# HVcontroller0_1.net
KiCad netlist of a schematic drawn in EAGLE
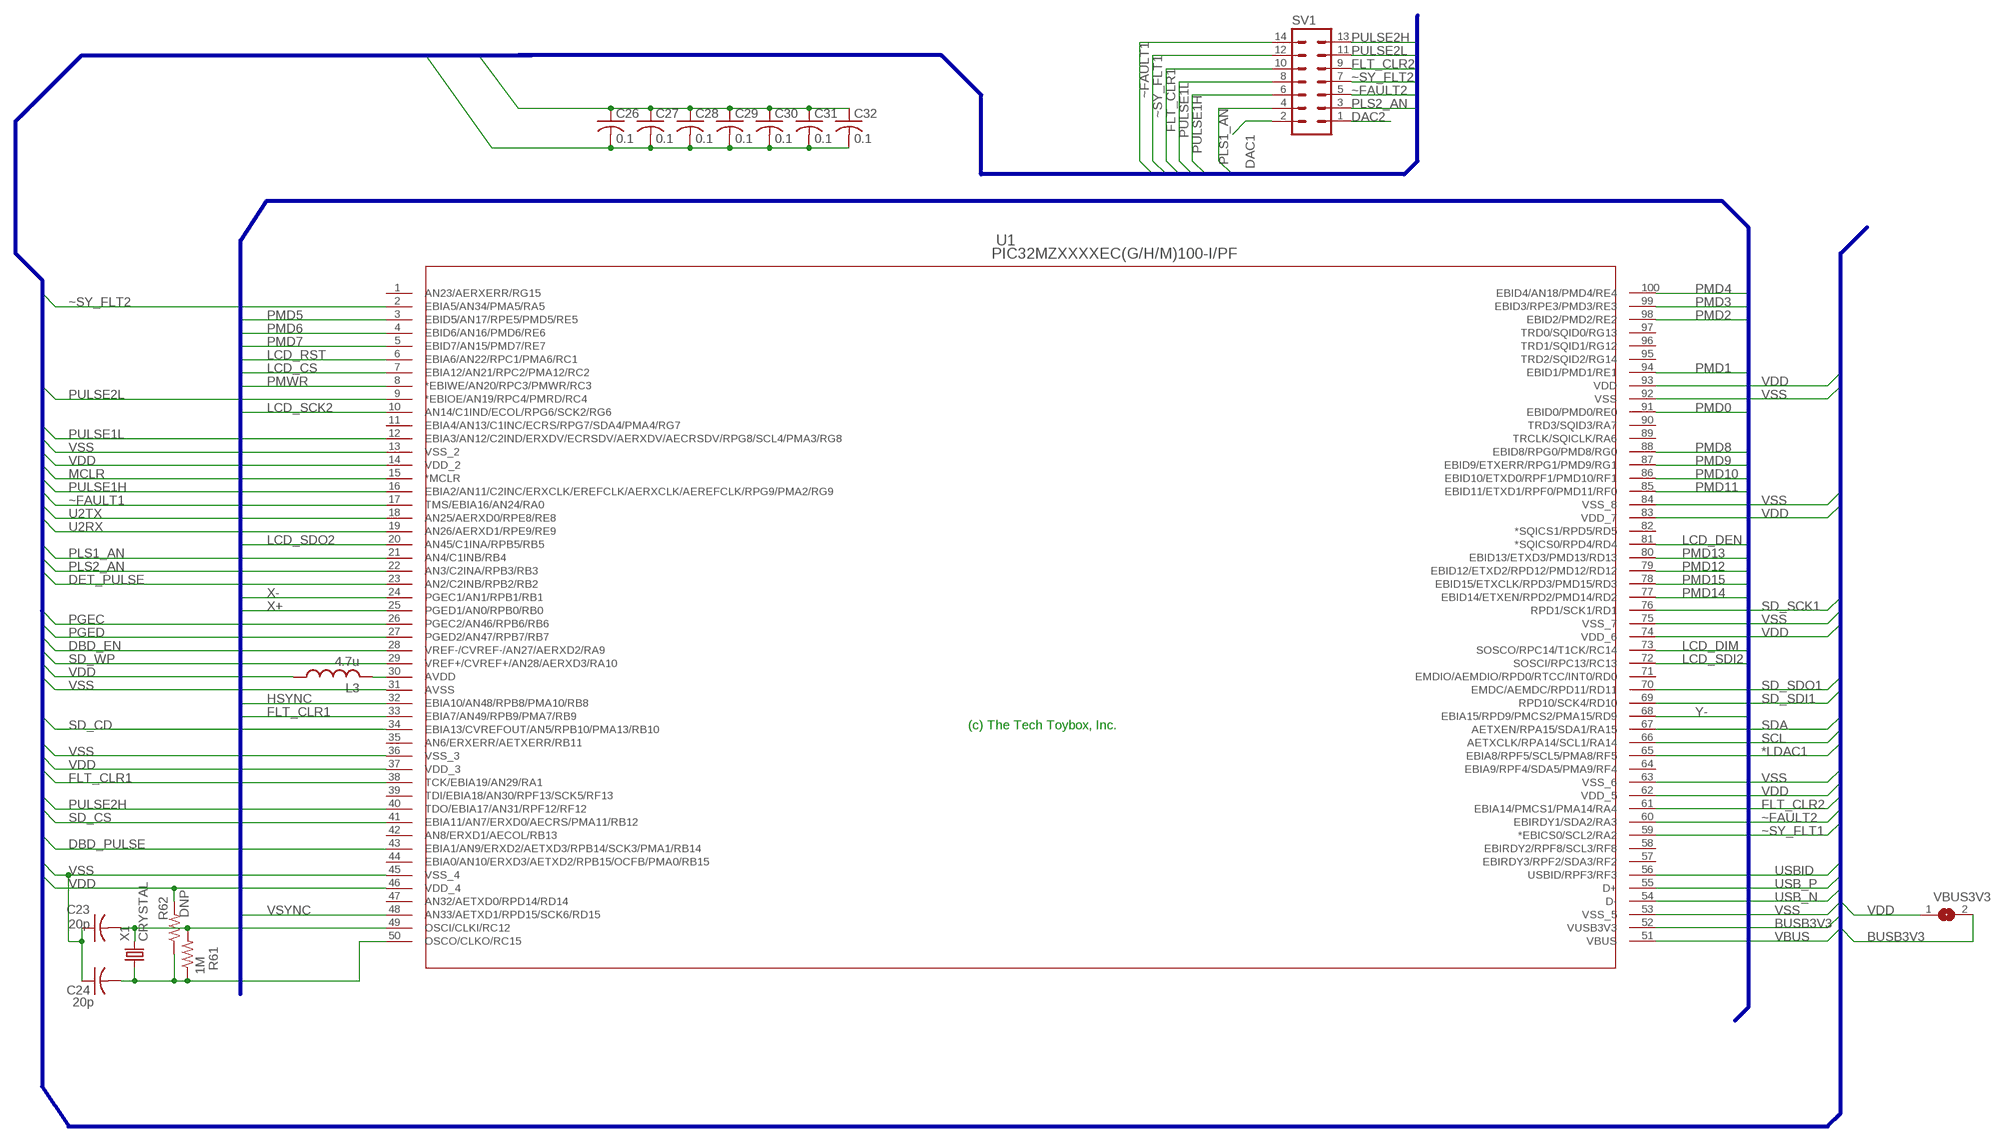
[diagram p0: schematic, sheet 1]
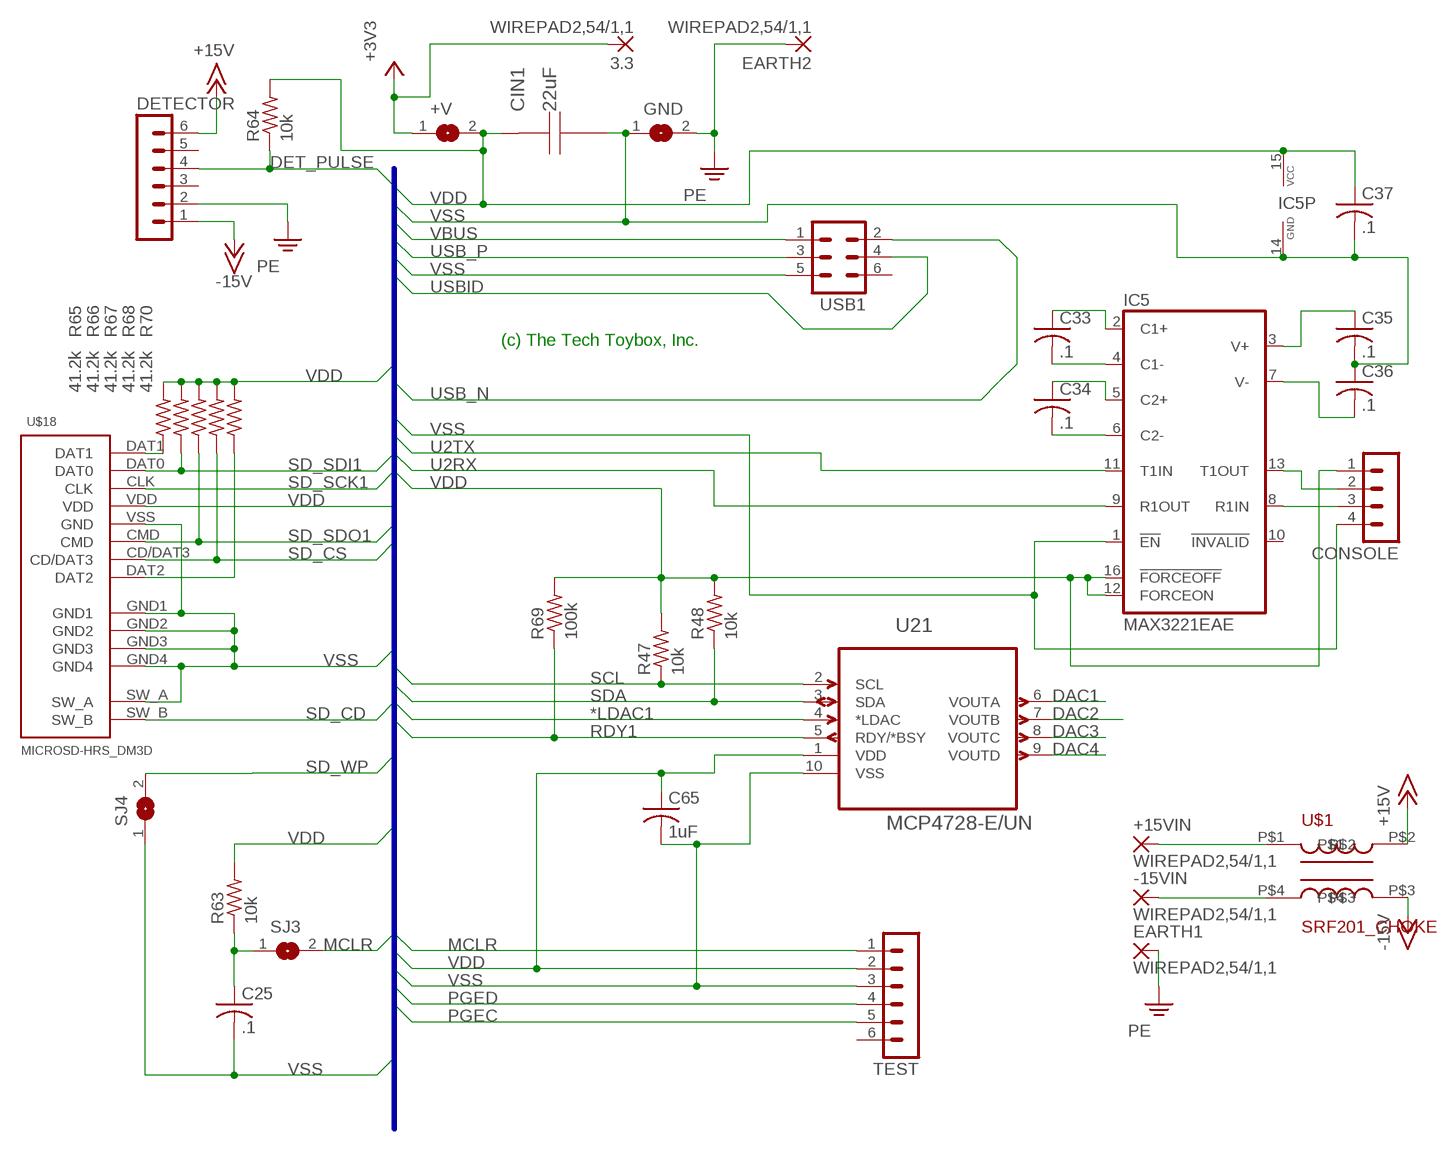
[diagram p1: schematic, sheet 2]

(export (version "E")
  (design (tool "Eeschema 10.0.6"))
  (components
    (comp (ref "C23")
      (value "20p")
      (footprint "eagle-import:C0402")
      (libsource (lib "eagle-import") (part "C-USC0402"))
    )
    (comp (ref "C24")
      (value "20p")
      (footprint "eagle-import:C0402")
      (libsource (lib "eagle-import") (part "C-USC0402"))
    )
    (comp (ref "C26")
      (value "0.1")
      (footprint "eagle-import:C0603")
      (libsource (lib "eagle-import") (part "C-USC0603"))
    )
    (comp (ref "C27")
      (value "0.1")
      (footprint "eagle-import:C0603")
      (libsource (lib "eagle-import") (part "C-USC0603"))
    )
    (comp (ref "C28")
      (value "0.1")
      (footprint "eagle-import:C0603")
      (libsource (lib "eagle-import") (part "C-USC0603"))
    )
    (comp (ref "C29")
      (value "0.1")
      (footprint "eagle-import:C0603")
      (libsource (lib "eagle-import") (part "C-USC0603"))
    )
    (comp (ref "C30")
      (value "0.1")
      (footprint "eagle-import:C0603")
      (libsource (lib "eagle-import") (part "C-USC0603"))
    )
    (comp (ref "C31")
      (value "0.1")
      (footprint "eagle-import:C0603")
      (libsource (lib "eagle-import") (part "C-USC0603"))
    )
    (comp (ref "C32")
      (value "0.1")
      (footprint "eagle-import:C0603")
      (libsource (lib "eagle-import") (part "C-USC0603"))
    )
    (comp (ref "L3")
      (value "4.7u")
      (footprint "eagle-import:L2012C")
      (libsource (lib "eagle-import") (part "L-USL2012C"))
    )
    (comp (ref "R61")
      (value "1M")
      (footprint "eagle-import:R0402")
      (libsource (lib "eagle-import") (part "R-US_R0402"))
    )
    (comp (ref "R62")
      (value "DNP")
      (footprint "eagle-import:R0402")
      (libsource (lib "eagle-import") (part "R-US_R0402"))
    )
    (comp (ref "SV1")
      (value "MA07-2")
      (footprint "eagle-import:MA07-2")
      (libsource (lib "eagle-import") (part "MA07-2"))
    )
    (comp (ref "U1")
      (value "PIC32MZXXXXEC(G/H/M)100-I/PF")
      (footprint "eagle-import:TQFP100_14X14MC")
      (fields (field (name "MANUFACTURER_PART_NUMBER") "pic32mz1024ecg100-i/pf"))
      (libsource (lib "eagle-import") (part "PIC32MZXXXXEC(G/H/M)100-I/PF"))
    )
    (comp (ref "VBUS3V3")
      (value "SJ")
      (footprint "eagle-import:SJ")
      (libsource (lib "eagle-import") (part "SJ"))
    )
    (comp (ref "X1")
      (value "CRYSTAL")
      (footprint "eagle-import:ABM")
      (libsource (lib "eagle-import") (part "CRYSTAL"))
    )
    (comp (ref "+15VIN")
      (value "WIREPAD2,54/1,1")
      (footprint "eagle-import:2,54_1,1")
      (libsource (lib "eagle-import") (part "WIREPAD2,54/1,1"))
    )
    (comp (ref "+V")
      (value "SJW")
      (footprint "eagle-import:SJW")
      (libsource (lib "eagle-import") (part "SJW"))
    )
    (comp (ref "-15VIN")
      (value "WIREPAD2,54/1,1")
      (footprint "eagle-import:2,54_1,1")
      (libsource (lib "eagle-import") (part "WIREPAD2,54/1,1"))
    )
    (comp (ref "3.3")
      (value "WIREPAD2,54/1,1")
      (footprint "eagle-import:2,54_1,1")
      (libsource (lib "eagle-import") (part "WIREPAD2,54/1,1"))
    )
    (comp (ref "C25")
      (value ".1")
      (footprint "eagle-import:C0402")
      (libsource (lib "eagle-import") (part "C-USC0402"))
    )
    (comp (ref "C33")
      (value ".1")
      (footprint "eagle-import:C0402")
      (libsource (lib "eagle-import") (part "C-USC0402"))
    )
    (comp (ref "C34")
      (value ".1")
      (footprint "eagle-import:C0402")
      (libsource (lib "eagle-import") (part "C-USC0402"))
    )
    (comp (ref "C35")
      (value ".1")
      (footprint "eagle-import:C0402")
      (libsource (lib "eagle-import") (part "C-USC0402"))
    )
    (comp (ref "C36")
      (value ".1")
      (footprint "eagle-import:C0402")
      (libsource (lib "eagle-import") (part "C-USC0402"))
    )
    (comp (ref "C37")
      (value ".1")
      (footprint "eagle-import:C0402")
      (libsource (lib "eagle-import") (part "C-USC0402"))
    )
    (comp (ref "C65")
      (value "1uF")
      (footprint "eagle-import:C0402")
      (libsource (lib "eagle-import") (part "C-USC0402"))
    )
    (comp (ref "CIN1")
      (value "22uF")
      (footprint "eagle-import:1210")
      (fields (field (name "MANUFACTURER_PART_NUMBER") "GRM32ER61E226KE15L"))
      (libsource (lib "eagle-import") (part "GRM32ER61E226KE15L"))
    )
    (comp (ref "CONSOLE")
      (value "MA04-1")
      (footprint "eagle-import:MA04-1")
      (libsource (lib "eagle-import") (part "MA04-1"))
    )
    (comp (ref "DETECTOR")
      (value "MA06-1")
      (footprint "eagle-import:MA06-1")
      (libsource (lib "eagle-import") (part "MA06-1"))
    )
    (comp (ref "EARTH1")
      (value "WIREPAD2,54/1,1")
      (footprint "eagle-import:2,54_1,1")
      (libsource (lib "eagle-import") (part "WIREPAD2,54/1,1"))
    )
    (comp (ref "EARTH2")
      (value "WIREPAD2,54/1,1")
      (footprint "eagle-import:2,54_1,1")
      (libsource (lib "eagle-import") (part "WIREPAD2,54/1,1"))
    )
    (comp (ref "GND")
      (value "SJW")
      (footprint "eagle-import:SJW")
      (libsource (lib "eagle-import") (part "SJW"))
    )
    (comp (ref "IC5")
      (value "MAX3221EAE")
      (footprint "eagle-import:SSOP16")
      (fields (field (name "MF") "MAXIM") (field (name "MPN") "MAX3221EAE+"))
      (libsource (lib "eagle-import") (part "MAX3221AEE"))
    )
    (comp (ref "R47")
      (value "10k")
      (footprint "eagle-import:R0805")
      (libsource (lib "eagle-import") (part "R-US_R0805"))
    )
    (comp (ref "R48")
      (value "10k")
      (footprint "eagle-import:R0805")
      (libsource (lib "eagle-import") (part "R-US_R0805"))
    )
    (comp (ref "R63")
      (value "10k")
      (footprint "eagle-import:R0805")
      (libsource (lib "eagle-import") (part "R-US_R0805"))
    )
    (comp (ref "R64")
      (value "10k")
      (footprint "eagle-import:R0805")
      (libsource (lib "eagle-import") (part "R-US_R0805"))
    )
    (comp (ref "R65")
      (value "41.2k")
      (footprint "eagle-import:R0603")
      (libsource (lib "eagle-import") (part "R-US_R0603"))
    )
    (comp (ref "R66")
      (value "41.2k")
      (footprint "eagle-import:R0603")
      (libsource (lib "eagle-import") (part "R-US_R0603"))
    )
    (comp (ref "R67")
      (value "41.2k")
      (footprint "eagle-import:R0603")
      (libsource (lib "eagle-import") (part "R-US_R0603"))
    )
    (comp (ref "R68")
      (value "41.2k")
      (footprint "eagle-import:R0603")
      (libsource (lib "eagle-import") (part "R-US_R0603"))
    )
    (comp (ref "R69")
      (value "100k")
      (footprint "eagle-import:R0805")
      (libsource (lib "eagle-import") (part "R-US_R0805"))
    )
    (comp (ref "R70")
      (value "41.2k")
      (footprint "eagle-import:R0603")
      (libsource (lib "eagle-import") (part "R-US_R0603"))
    )
    (comp (ref "SJ3") (value "SJ") (footprint "eagle-import:SJ") (libsource (lib "eagle-import") (part "SJ")))
    (comp (ref "SJ4") (value "SJ") (footprint "eagle-import:SJ") (libsource (lib "eagle-import") (part "SJ")))
    (comp (ref "TEST")
      (value "MA06-1")
      (footprint "eagle-import:MA06-1")
      (libsource (lib "eagle-import") (part "MA06-1"))
    )
    (comp (ref "U$1")
      (value "SRF201_CHOKE")
      (footprint "eagle-import:CHOKE_BOURNES_SRF2012")
      (libsource (lib "eagle-import") (part "SRF201_CHOKE"))
    )
    (comp (ref "U$18")
      (value "MICROSD-HRS_DM3D")
      (footprint "eagle-import:DM3D")
      (libsource (lib "eagle-import") (part "MICROSD-HRS_DM3D"))
    )
    (comp (ref "U21")
      (value "MCP4728-E/UN")
      (footprint "eagle-import:SOP50P490X110-10N")
      (libsource (lib "eagle-import") (part "MCP4728-E/UN"))
    )
    (comp (ref "USB1")
      (value "MA03-2")
      (footprint "eagle-import:MA03-2")
      (libsource (lib "eagle-import") (part "MA03-2"))
    )
  )
  (nets
    (net (code "1") (name "*LDAC1") (class "Default")
      (node (ref "U1") (pin "65") (pinfunction "EBIA8/RPF5/SCL5/PMA8/RF5_65") (pintype "bidirectional"))
      (node (ref "U21") (pin "4") (pinfunction "*LDAC_4") (pintype "input"))
    )
    (net (code "2") (name "+3V3") (class "Default")
      (node (ref "+V") (pin "1") (pinfunction "1_1") (pintype "passive"))
      (node (ref "3.3") (pin "1") (pinfunction "P_1") (pintype "passive"))
    )
    (net (code "3") (name "+15V") (class "Default")
      (node (ref "DETECTOR") (pin "6") (pinfunction "6_6") (pintype "passive"))
      (node (ref "U$1") (pin "P$2") (pinfunction "P$2_P$2") (pintype "bidirectional"))
    )
    (net (code "4") (name "-15V") (class "Default")
      (node (ref "DETECTOR") (pin "1") (pinfunction "1_1") (pintype "passive"))
      (node (ref "U$1") (pin "P$3") (pinfunction "P$3_P$3") (pintype "bidirectional"))
    )
    (net (code "5") (name "BUSB3V3") (class "Default")
      (node (ref "U1") (pin "52") (pinfunction "VUSB3V3_52") (pintype "power_in"))
      (node (ref "VBUS3V3") (pin "2") (pinfunction "2_2") (pintype "passive"))
    )
    (net (code "6") (name "DAC1") (class "Default")
      (node (ref "SV1") (pin "2") (pinfunction "2_2") (pintype "passive"))
      (node (ref "U21") (pin "6") (pinfunction "VOUTA_6") (pintype "output"))
    )
    (net (code "7") (name "DAC2") (class "Default")
      (node (ref "SV1") (pin "1") (pinfunction "1_1") (pintype "passive"))
      (node (ref "U21") (pin "7") (pinfunction "VOUTB_7") (pintype "output"))
    )
    (net (code "8") (name "DAC3") (class "Default")
      (node (ref "U21") (pin "8") (pinfunction "VOUTC_8") (pintype "output"))
    )
    (net (code "9") (name "DAC4") (class "Default")
      (node (ref "U21") (pin "9") (pinfunction "VOUTD_9") (pintype "output"))
    )
    (net (code "10") (name "DBD_EN") (class "Default")
      (node (ref "U1") (pin "28") (pinfunction "VREF-/CVREF-/AN27/AERXD2/RA9_28") (pintype "bidirectional"))
    )
    (net (code "11") (name "DBD_PULSE") (class "Default")
      (node (ref "U1") (pin "43") (pinfunction "EBIA1/AN9/ERXD2/AETXD3/RPB14/SCK3/PMA1/RB14_43") (pintype "bidirectional"))
    )
    (net (code "12") (name "DET_PULSE") (class "Default")
      (node (ref "DETECTOR") (pin "4") (pinfunction "4_4") (pintype "passive"))
      (node (ref "R64") (pin "1") (pinfunction "1_1") (pintype "passive"))
      (node (ref "U1") (pin "23") (pinfunction "AN2/C2INB/RPB2/RB2_23") (pintype "bidirectional"))
    )
    (net (code "13") (name "FLT_CLR1") (class "Default")
      (node (ref "SV1") (pin "10") (pinfunction "10_10") (pintype "passive"))
      (node (ref "U1") (pin "38") (pinfunction "TCK/EBIA19/AN29/RA1_38") (pintype "bidirectional"))
    )
    (net (code "14") (name "FLT_CLR2") (class "Default")
      (node (ref "SV1") (pin "9") (pinfunction "9_9") (pintype "passive"))
      (node (ref "U1") (pin "61") (pinfunction "EBIA14/PMCS1/PMA14/RA4_61") (pintype "bidirectional"))
    )
    (net (code "15") (name "HSYNC") (class "Default")
      (node (ref "U1") (pin "32") (pinfunction "EBIA10/AN48/RPB8/PMA10/RB8_32") (pintype "bidirectional"))
    )
    (net (code "16") (name "LCD_CS") (class "Default")
      (node (ref "U1") (pin "7") (pinfunction "EBIA12/AN21/RPC2/PMA12/RC2_7") (pintype "bidirectional"))
    )
    (net (code "17") (name "LCD_DEN") (class "Default")
      (node (ref "U1") (pin "81") (pinfunction "*SQICS0/RPD4/RD4_81") (pintype "bidirectional"))
    )
    (net (code "18") (name "LCD_DIM") (class "Default")
      (node (ref "U1") (pin "73") (pinfunction "SOSCO/RPC14/T1CK/RC14_73") (pintype "bidirectional"))
    )
    (net (code "19") (name "LCD_RST") (class "Default")
      (node (ref "U1") (pin "6") (pinfunction "EBIA6/AN22/RPC1/PMA6/RC1_6") (pintype "bidirectional"))
    )
    (net (code "20") (name "LCD_SCK2") (class "Default")
      (node (ref "U1") (pin "10") (pinfunction "AN14/C1IND/ECOL/RPG6/SCK2/RG6_10") (pintype "bidirectional"))
    )
    (net (code "21") (name "LCD_SDI2") (class "Default")
      (node (ref "U1") (pin "72") (pinfunction "SOSCI/RPC13/RC13_72") (pintype "bidirectional"))
    )
    (net (code "22") (name "LCD_SDO2") (class "Default")
      (node (ref "U1") (pin "20") (pinfunction "AN45/C1INA/RPB5/RB5_20") (pintype "bidirectional"))
    )
    (net (code "23") (name "MCLR") (class "Default")
      (node (ref "SJ3") (pin "2") (pinfunction "2_2") (pintype "passive"))
      (node (ref "TEST") (pin "1") (pinfunction "1_1") (pintype "passive"))
      (node (ref "U1") (pin "15") (pinfunction "*MCLR_15") (pintype "passive"))
    )
    (net (code "24") (name "Net-(+15VIN-P)") (class "Default")
      (node (ref "+15VIN") (pin "1") (pinfunction "P_1") (pintype "passive"))
      (node (ref "U$1") (pin "P$1") (pinfunction "P$1_P$1") (pintype "bidirectional"))
    )
    (net (code "25") (name "Net-(-15VIN-P)") (class "Default")
      (node (ref "-15VIN") (pin "1") (pinfunction "P_1") (pintype "passive"))
      (node (ref "U$1") (pin "P$4") (pinfunction "P$4_P$4") (pintype "bidirectional"))
    )
    (net (code "26") (name "Net-(C25-Pad1)") (class "Default")
      (node (ref "C25") (pin "1") (pinfunction "1_1") (pintype "passive"))
      (node (ref "R63") (pin "1") (pinfunction "1_1") (pintype "passive"))
      (node (ref "SJ3") (pin "1") (pinfunction "1_1") (pintype "passive"))
    )
    (net (code "27") (name "Net-(IC5A-C1+)") (class "Default")
      (node (ref "C33") (pin "1") (pinfunction "1_1") (pintype "passive"))
      (node (ref "IC5") (pin "2") (pinfunction "C1+_2") (pintype "passive"))
    )
    (net (code "28") (name "Net-(IC5A-C1-)") (class "Default")
      (node (ref "C33") (pin "2") (pinfunction "2_2") (pintype "passive"))
      (node (ref "IC5") (pin "4") (pinfunction "C1-_4") (pintype "passive"))
    )
    (net (code "29") (name "Net-(IC5A-C2+)") (class "Default")
      (node (ref "C34") (pin "1") (pinfunction "1_1") (pintype "passive"))
      (node (ref "IC5") (pin "5") (pinfunction "C2+_5") (pintype "passive"))
    )
    (net (code "30") (name "Net-(IC5A-C2-)") (class "Default")
      (node (ref "C34") (pin "2") (pinfunction "2_2") (pintype "passive"))
      (node (ref "IC5") (pin "6") (pinfunction "C2-_6") (pintype "passive"))
    )
    (net (code "31") (name "Net-(IC5A-R1IN)") (class "Default")
      (node (ref "CONSOLE") (pin "3") (pinfunction "3_3") (pintype "passive"))
      (node (ref "IC5") (pin "8") (pinfunction "R1IN_8") (pintype "input"))
    )
    (net (code "32") (name "Net-(IC5A-T1OUT)") (class "Default")
      (node (ref "CONSOLE") (pin "2") (pinfunction "2_2") (pintype "passive"))
      (node (ref "IC5") (pin "13") (pinfunction "T1OUT_13") (pintype "output"))
    )
    (net (code "33") (name "Net-(IC5A-V+)") (class "Default")
      (node (ref "C35") (pin "1") (pinfunction "1_1") (pintype "passive"))
      (node (ref "IC5") (pin "3") (pinfunction "V+_3") (pintype "passive"))
    )
    (net (code "34") (name "Net-(IC5A-V-)") (class "Default")
      (node (ref "C36") (pin "2") (pinfunction "2_2") (pintype "passive"))
      (node (ref "IC5") (pin "7") (pinfunction "V-_7") (pintype "passive"))
    )
    (net (code "35") (name "Net-(R65-Pad1)") (class "Default")
      (node (ref "R65") (pin "1") (pinfunction "1_1") (pintype "passive"))
      (node (ref "U$18") (pin "DAT1") (pinfunction "DAT1_DAT1") (pintype "bidirectional"))
    )
    (net (code "36") (name "Net-(R70-Pad1)") (class "Default")
      (node (ref "R70") (pin "1") (pinfunction "1_1") (pintype "passive"))
      (node (ref "U$18") (pin "DAT2") (pinfunction "DAT2_DAT2") (pintype "bidirectional"))
    )
    (net (code "37") (name "Net-(U1-AVDD)") (class "Default")
      (node (ref "L3") (pin "2") (pinfunction "2_2") (pintype "passive"))
      (node (ref "U1") (pin "30") (pinfunction "AVDD_30") (pintype "power_in"))
    )
    (net (code "38") (name "Net-(U1-OSCI{slash}CLKI{slash}RC12)") (class "Default")
      (node (ref "C23") (pin "2") (pinfunction "2_2") (pintype "passive"))
      (node (ref "R61") (pin "2") (pinfunction "2_2") (pintype "passive"))
      (node (ref "U1") (pin "49") (pinfunction "OSCI/CLKI/RC12_49") (pintype "bidirectional"))
      (node (ref "X1") (pin "P$2") (pinfunction "2_P$2") (pintype "passive"))
    )
    (net (code "39") (name "Net-(U1-OSCO{slash}CLKO{slash}RC15)") (class "Default")
      (node (ref "C24") (pin "2") (pinfunction "2_2") (pintype "passive"))
      (node (ref "R61") (pin "1") (pinfunction "1_1") (pintype "passive"))
      (node (ref "R62") (pin "1") (pinfunction "1_1") (pintype "passive"))
      (node (ref "U1") (pin "50") (pinfunction "OSCO/CLKO/RC15_50") (pintype "bidirectional"))
      (node (ref "X1") (pin "P$1") (pinfunction "1_P$1") (pintype "passive"))
    )
    (net (code "40") (name "PE") (class "Default")
      (node (ref "DETECTOR") (pin "2") (pinfunction "2_2") (pintype "passive"))
      (node (ref "EARTH1") (pin "1") (pinfunction "P_1") (pintype "passive"))
      (node (ref "EARTH2") (pin "1") (pinfunction "P_1") (pintype "passive"))
      (node (ref "GND") (pin "2") (pinfunction "2_2") (pintype "passive"))
    )
    (net (code "41") (name "PGEC") (class "Default")
      (node (ref "TEST") (pin "5") (pinfunction "5_5") (pintype "passive"))
      (node (ref "U1") (pin "26") (pinfunction "PGEC2/AN46/RPB6/RB6_26") (pintype "bidirectional"))
    )
    (net (code "42") (name "PGED") (class "Default")
      (node (ref "TEST") (pin "4") (pinfunction "4_4") (pintype "passive"))
      (node (ref "U1") (pin "27") (pinfunction "PGED2/AN47/RPB7/RB7_27") (pintype "bidirectional"))
    )
    (net (code "43") (name "PLS1_AN") (class "Default")
      (node (ref "SV1") (pin "4") (pinfunction "4_4") (pintype "passive"))
      (node (ref "U1") (pin "21") (pinfunction "AN4/C1INB/RB4_21") (pintype "bidirectional"))
    )
    (net (code "44") (name "PLS2_AN") (class "Default")
      (node (ref "SV1") (pin "3") (pinfunction "3_3") (pintype "passive"))
      (node (ref "U1") (pin "22") (pinfunction "AN3/C2INA/RPB3/RB3_22") (pintype "bidirectional"))
    )
    (net (code "45") (name "PMD0") (class "Default")
      (node (ref "U1") (pin "91") (pinfunction "EBID0/PMD0/RE0_91") (pintype "bidirectional"))
    )
    (net (code "46") (name "PMD1") (class "Default")
      (node (ref "U1") (pin "94") (pinfunction "EBID1/PMD1/RE1_94") (pintype "bidirectional"))
    )
    (net (code "47") (name "PMD2") (class "Default")
      (node (ref "U1") (pin "98") (pinfunction "EBID2/PMD2/RE2_98") (pintype "bidirectional"))
    )
    (net (code "48") (name "PMD3") (class "Default")
      (node (ref "U1") (pin "99") (pinfunction "EBID3/RPE3/PMD3/RE3_99") (pintype "bidirectional"))
    )
    (net (code "49") (name "PMD4") (class "Default")
      (node (ref "U1") (pin "100") (pinfunction "EBID4/AN18/PMD4/RE4_100") (pintype "bidirectional"))
    )
    (net (code "50") (name "PMD5") (class "Default")
      (node (ref "U1") (pin "3") (pinfunction "EBID5/AN17/RPE5/PMD5/RE5_3") (pintype "bidirectional"))
    )
    (net (code "51") (name "PMD6") (class "Default")
      (node (ref "U1") (pin "4") (pinfunction "EBID6/AN16/PMD6/RE6_4") (pintype "bidirectional"))
    )
    (net (code "52") (name "PMD7") (class "Default")
      (node (ref "U1") (pin "5") (pinfunction "EBID7/AN15/PMD7/RE7_5") (pintype "bidirectional"))
    )
    (net (code "53") (name "PMD8") (class "Default")
      (node (ref "U1") (pin "88") (pinfunction "EBID8/RPG0/PMD8/RG0_88") (pintype "bidirectional"))
    )
    (net (code "54") (name "PMD9") (class "Default")
      (node (ref "U1") (pin "87") (pinfunction "EBID9/ETXERR/RPG1/PMD9/RG1_87") (pintype "bidirectional"))
    )
    (net (code "55") (name "PMD10") (class "Default")
      (node (ref "U1") (pin "86") (pinfunction "EBID10/ETXD0/RPF1/PMD10/RF1_86") (pintype "bidirectional"))
    )
    (net (code "56") (name "PMD11") (class "Default")
      (node (ref "U1") (pin "85") (pinfunction "EBID11/ETXD1/RPF0/PMD11/RF0_85") (pintype "bidirectional"))
    )
    (net (code "57") (name "PMD12") (class "Default")
      (node (ref "U1") (pin "79") (pinfunction "EBID12/ETXD2/RPD12/PMD12/RD12_79") (pintype "bidirectional"))
    )
    (net (code "58") (name "PMD13") (class "Default")
      (node (ref "U1") (pin "80") (pinfunction "EBID13/ETXD3/PMD13/RD13_80") (pintype "bidirectional"))
    )
    (net (code "59") (name "PMD14") (class "Default")
      (node (ref "U1") (pin "77") (pinfunction "EBID14/ETXEN/RPD2/PMD14/RD2_77") (pintype "bidirectional"))
    )
    (net (code "60") (name "PMD15") (class "Default")
      (node (ref "U1") (pin "78") (pinfunction "EBID15/ETXCLK/RPD3/PMD15/RD3_78") (pintype "bidirectional"))
    )
    (net (code "61") (name "PMWR") (class "Default")
      (node (ref "U1") (pin "8") (pinfunction "*EBIWE/AN20/RPC3/PMWR/RC3_8") (pintype "bidirectional"))
    )
    (net (code "62") (name "PULSE1H") (class "Default")
      (node (ref "SV1") (pin "6") (pinfunction "6_6") (pintype "passive"))
      (node (ref "U1") (pin "16") (pinfunction "EBIA2/AN11/C2INC/ERXCLK/EREFCLK/AERXCLK/AEREFCLK/RPG9/PMA2/RG9_16") (pintype "bidirectional"))
    )
    (net (code "63") (name "PULSE1L") (class "Default")
      (node (ref "SV1") (pin "8") (pinfunction "8_8") (pintype "passive"))
      (node (ref "U1") (pin "12") (pinfunction "EBIA3/AN12/C2IND/ERXDV/ECRSDV/AERXDV/AECRSDV/RPG8/SCL4/PMA3/RG8_12") (pintype "bidirectional"))
    )
    (net (code "64") (name "PULSE2H") (class "Default")
      (node (ref "SV1") (pin "13") (pinfunction "13_13") (pintype "passive"))
      (node (ref "U1") (pin "40") (pinfunction "TDO/EBIA17/AN31/RPF12/RF12_40") (pintype "bidirectional"))
    )
    (net (code "65") (name "PULSE2L") (class "Default")
      (node (ref "SV1") (pin "11") (pinfunction "11_11") (pintype "passive"))
      (node (ref "U1") (pin "9") (pinfunction "*EBIOE/AN19/RPC4/PMRD/RC4_9") (pintype "bidirectional"))
    )
    (net (code "66") (name "RDY1") (class "Default")
      (node (ref "R69") (pin "1") (pinfunction "1_1") (pintype "passive"))
      (node (ref "U21") (pin "5") (pinfunction "RDY/*BSY_5") (pintype "output"))
    )
    (net (code "67") (name "SCL") (class "Default")
      (node (ref "R47") (pin "1") (pinfunction "1_1") (pintype "passive"))
      (node (ref "U1") (pin "66") (pinfunction "AETXCLK/RPA14/SCL1/RA14_66") (pintype "bidirectional"))
      (node (ref "U21") (pin "2") (pinfunction "SCL_2") (pintype "input"))
    )
    (net (code "68") (name "SDA") (class "Default")
      (node (ref "R48") (pin "1") (pinfunction "1_1") (pintype "passive"))
      (node (ref "U1") (pin "67") (pinfunction "AETXEN/RPA15/SDA1/RA15_67") (pintype "bidirectional"))
      (node (ref "U21") (pin "3") (pinfunction "SDA_3") (pintype "bidirectional"))
    )
    (net (code "69") (name "SD_CD") (class "Default")
      (node (ref "U$18") (pin "SW_B") (pinfunction "SW_B_SW_B") (pintype "bidirectional"))
      (node (ref "U1") (pin "34") (pinfunction "EBIA13/CVREFOUT/AN5/RPB10/PMA13/RB10_34") (pintype "bidirectional"))
    )
    (net (code "70") (name "SD_CS") (class "Default")
      (node (ref "R68") (pin "1") (pinfunction "1_1") (pintype "passive"))
      (node (ref "U$18") (pin "CD/DAT3") (pinfunction "CD/DAT3_CD/DAT3") (pintype "bidirectional"))
      (node (ref "U1") (pin "41") (pinfunction "EBIA11/AN7/ERXD0/AECRS/PMA11/RB12_41") (pintype "bidirectional"))
    )
    (net (code "71") (name "SD_SCK1") (class "Default")
      (node (ref "U$18") (pin "CLK") (pinfunction "CLK_CLK") (pintype "bidirectional"))
      (node (ref "U1") (pin "76") (pinfunction "RPD1/SCK1/RD1_76") (pintype "bidirectional"))
    )
    (net (code "72") (name "SD_SDI1") (class "Default")
      (node (ref "R66") (pin "1") (pinfunction "1_1") (pintype "passive"))
      (node (ref "U$18") (pin "DAT0") (pinfunction "DAT0_DAT0") (pintype "bidirectional"))
      (node (ref "U1") (pin "69") (pinfunction "RPD10/SCK4/RD10_69") (pintype "bidirectional"))
    )
    (net (code "73") (name "SD_SDO1") (class "Default")
      (node (ref "R67") (pin "1") (pinfunction "1_1") (pintype "passive"))
      (node (ref "U$18") (pin "CMD") (pinfunction "CMD_CMD") (pintype "bidirectional"))
      (node (ref "U1") (pin "70") (pinfunction "EMDC/AEMDC/RPD11/RD11_70") (pintype "bidirectional"))
    )
    (net (code "74") (name "SD_WP") (class "Default")
      (node (ref "SJ4") (pin "2") (pinfunction "2_2") (pintype "passive"))
      (node (ref "U1") (pin "29") (pinfunction "VREF+/CVREF+/AN28/AERXD3/RA10_29") (pintype "bidirectional"))
    )
    (net (code "75") (name "U2RX") (class "Default")
      (node (ref "IC5") (pin "9") (pinfunction "R1OUT_9") (pintype "output"))
      (node (ref "U1") (pin "19") (pinfunction "AN26/AERXD1/RPE9/RE9_19") (pintype "bidirectional"))
    )
    (net (code "76") (name "U2TX") (class "Default")
      (node (ref "IC5") (pin "11") (pinfunction "T1IN_11") (pintype "input"))
      (node (ref "U1") (pin "18") (pinfunction "AN25/AERXD0/RPE8/RE8_18") (pintype "bidirectional"))
    )
    (net (code "77") (name "USBID") (class "Default")
      (node (ref "U1") (pin "56") (pinfunction "USBID/RPF3/RF3_56") (pintype "bidirectional"))
      (node (ref "USB1") (pin "4") (pinfunction "4_4") (pintype "passive"))
    )
    (net (code "78") (name "USB_N") (class "Default")
      (node (ref "U1") (pin "54") (pinfunction "D-_54") (pintype "passive"))
      (node (ref "USB1") (pin "2") (pinfunction "2_2") (pintype "passive"))
    )
    (net (code "79") (name "USB_P") (class "Default")
      (node (ref "U1") (pin "55") (pinfunction "D+_55") (pintype "passive"))
      (node (ref "USB1") (pin "3") (pinfunction "3_3") (pintype "passive"))
    )
    (net (code "80") (name "VBUS") (class "Default")
      (node (ref "U1") (pin "51") (pinfunction "VBUS_51") (pintype "power_in"))
      (node (ref "USB1") (pin "1") (pinfunction "1_1") (pintype "passive"))
    )
    (net (code "81") (name "VDD") (class "Default")
      (node (ref "+V") (pin "2") (pinfunction "2_2") (pintype "passive"))
      (node (ref "C26") (pin "1") (pinfunction "1_1") (pintype "passive"))
      (node (ref "C27") (pin "1") (pinfunction "1_1") (pintype "passive"))
      (node (ref "C28") (pin "1") (pinfunction "1_1") (pintype "passive"))
      (node (ref "C29") (pin "1") (pinfunction "1_1") (pintype "passive"))
      (node (ref "C30") (pin "1") (pinfunction "1_1") (pintype "passive"))
      (node (ref "C31") (pin "1") (pinfunction "1_1") (pintype "passive"))
      (node (ref "C32") (pin "1") (pinfunction "1_1") (pintype "passive"))
      (node (ref "C37") (pin "1") (pinfunction "1_1") (pintype "passive"))
      (node (ref "C65") (pin "1") (pinfunction "1_1") (pintype "passive"))
      (node (ref "CIN1") (pin "1") (pinfunction "1_1") (pintype "passive"))
      (node (ref "CONSOLE") (pin "1") (pinfunction "1_1") (pintype "passive"))
      (node (ref "IC5") (pin "12") (pinfunction "FORCEON_12") (pintype "input"))
      (node (ref "IC5") (pin "15") (pinfunction "VCC_15") (pintype "power_in"))
      (node (ref "IC5") (pin "16") (pinfunction "~{FORCEOFF}_16") (pintype "input"))
      (node (ref "L3") (pin "1") (pinfunction "1_1") (pintype "passive"))
      (node (ref "R47") (pin "2") (pinfunction "2_2") (pintype "passive"))
      (node (ref "R48") (pin "2") (pinfunction "2_2") (pintype "passive"))
      (node (ref "R62") (pin "2") (pinfunction "2_2") (pintype "passive"))
      (node (ref "R63") (pin "2") (pinfunction "2_2") (pintype "passive"))
      (node (ref "R64") (pin "2") (pinfunction "2_2") (pintype "passive"))
      (node (ref "R65") (pin "2") (pinfunction "2_2") (pintype "passive"))
      (node (ref "R66") (pin "2") (pinfunction "2_2") (pintype "passive"))
      (node (ref "R67") (pin "2") (pinfunction "2_2") (pintype "passive"))
      (node (ref "R68") (pin "2") (pinfunction "2_2") (pintype "passive"))
      (node (ref "R69") (pin "2") (pinfunction "2_2") (pintype "passive"))
      (node (ref "R70") (pin "2") (pinfunction "2_2") (pintype "passive"))
      (node (ref "TEST") (pin "2") (pinfunction "2_2") (pintype "passive"))
      (node (ref "U$18") (pin "VDD") (pinfunction "VDD_VDD") (pintype "bidirectional"))
      (node (ref "U1") (pin "14") (pinfunction "VDD_2_14") (pintype "power_in"))
      (node (ref "U1") (pin "37") (pinfunction "VDD_3_37") (pintype "power_in"))
      (node (ref "U1") (pin "46") (pinfunction "VDD_4_46") (pintype "power_in"))
      (node (ref "U1") (pin "62") (pinfunction "VDD_5_62") (pintype "power_in"))
      (node (ref "U1") (pin "74") (pinfunction "VDD_6_74") (pintype "power_in"))
      (node (ref "U1") (pin "83") (pinfunction "VDD_7_83") (pintype "power_in"))
      (node (ref "U1") (pin "93") (pinfunction "VDD_93") (pintype "power_in"))
      (node (ref "U21") (pin "1") (pinfunction "VDD_1") (pintype "power_in"))
      (node (ref "VBUS3V3") (pin "1") (pinfunction "1_1") (pintype "passive"))
    )
    (net (code "82") (name "VSS") (class "Default")
      (node (ref "C23") (pin "1") (pinfunction "1_1") (pintype "passive"))
      (node (ref "C24") (pin "1") (pinfunction "1_1") (pintype "passive"))
      (node (ref "C25") (pin "2") (pinfunction "2_2") (pintype "passive"))
      (node (ref "C26") (pin "2") (pinfunction "2_2") (pintype "passive"))
      (node (ref "C27") (pin "2") (pinfunction "2_2") (pintype "passive"))
      (node (ref "C28") (pin "2") (pinfunction "2_2") (pintype "passive"))
      (node (ref "C29") (pin "2") (pinfunction "2_2") (pintype "passive"))
      (node (ref "C30") (pin "2") (pinfunction "2_2") (pintype "passive"))
      (node (ref "C31") (pin "2") (pinfunction "2_2") (pintype "passive"))
      (node (ref "C32") (pin "2") (pinfunction "2_2") (pintype "passive"))
      (node (ref "C35") (pin "2") (pinfunction "2_2") (pintype "passive"))
      (node (ref "C36") (pin "1") (pinfunction "1_1") (pintype "passive"))
      (node (ref "C37") (pin "2") (pinfunction "2_2") (pintype "passive"))
      (node (ref "C65") (pin "2") (pinfunction "2_2") (pintype "passive"))
      (node (ref "CIN1") (pin "2") (pinfunction "2_2") (pintype "passive"))
      (node (ref "CONSOLE") (pin "4") (pinfunction "4_4") (pintype "passive"))
      (node (ref "GND") (pin "1") (pinfunction "1_1") (pintype "passive"))
      (node (ref "IC5") (pin "1") (pinfunction "~{EN}_1") (pintype "input"))
      (node (ref "IC5") (pin "14") (pinfunction "GND_14") (pintype "power_in"))
      (node (ref "SJ4") (pin "1") (pinfunction "1_1") (pintype "passive"))
      (node (ref "TEST") (pin "3") (pinfunction "3_3") (pintype "passive"))
      (node (ref "U$18") (pin "GND1") (pinfunction "GND1_GND1") (pintype "bidirectional"))
      (node (ref "U$18") (pin "GND2") (pinfunction "GND2_GND2") (pintype "bidirectional"))
      (node (ref "U$18") (pin "GND3") (pinfunction "GND3_GND3") (pintype "bidirectional"))
      (node (ref "U$18") (pin "GND4") (pinfunction "GND4_GND4") (pintype "bidirectional"))
      (node (ref "U$18") (pin "SW_A") (pinfunction "SW_A_SW_A") (pintype "bidirectional"))
      (node (ref "U$18") (pin "VSS") (pinfunction "GND_VSS") (pintype "bidirectional"))
      (node (ref "U1") (pin "13") (pinfunction "VSS_2_13") (pintype "power_in"))
      (node (ref "U1") (pin "31") (pinfunction "AVSS_31") (pintype "power_in"))
      (node (ref "U1") (pin "36") (pinfunction "VSS_3_36") (pintype "power_in"))
      (node (ref "U1") (pin "45") (pinfunction "VSS_4_45") (pintype "power_in"))
      (node (ref "U1") (pin "53") (pinfunction "VSS_5_53") (pintype "power_in"))
      (node (ref "U1") (pin "63") (pinfunction "VSS_6_63") (pintype "power_in"))
      (node (ref "U1") (pin "75") (pinfunction "VSS_7_75") (pintype "power_in"))
      (node (ref "U1") (pin "84") (pinfunction "VSS_8_84") (pintype "power_in"))
      (node (ref "U1") (pin "92") (pinfunction "VSS_92") (pintype "power_in"))
      (node (ref "U21") (pin "10") (pinfunction "VSS_10") (pintype "power_in"))
      (node (ref "USB1") (pin "5") (pinfunction "5_5") (pintype "passive"))
    )
    (net (code "83") (name "VSYNC") (class "Default")
      (node (ref "U1") (pin "48") (pinfunction "AN33/AETXD1/RPD15/SCK6/RD15_48") (pintype "bidirectional"))
    )
    (net (code "84") (name "X+") (class "Default")
      (node (ref "U1") (pin "25") (pinfunction "PGED1/AN0/RPB0/RB0_25") (pintype "bidirectional"))
    )
    (net (code "85") (name "X-") (class "Default")
      (node (ref "U1") (pin "24") (pinfunction "PGEC1/AN1/RPB1/RB1_24") (pintype "bidirectional"))
    )
    (net (code "86") (name "Y-") (class "Default")
      (node (ref "U1") (pin "68") (pinfunction "EBIA15/RPD9/PMCS2/PMA15/RD9_68") (pintype "bidirectional"))
    )
    (net (code "87") (name "unconnected-(DETECTOR-Pad3)") (class "Default")
      (node (ref "DETECTOR") (pin "3") (pinfunction "3_3") (pintype "passive"))
    )
    (net (code "88") (name "unconnected-(DETECTOR-Pad5)") (class "Default")
      (node (ref "DETECTOR") (pin "5") (pinfunction "5_5") (pintype "passive"))
    )
    (net (code "89") (name "unconnected-(IC5A-~{INVALID}-Pad10)") (class "Default")
      (node (ref "IC5") (pin "10") (pinfunction "~{INVALID}_10") (pintype "input"))
    )
    (net (code "90") (name "unconnected-(TEST-Pad6)") (class "Default")
      (node (ref "TEST") (pin "6") (pinfunction "6_6") (pintype "passive"))
    )
    (net (code "91") (name "unconnected-(U1-*SQICS1{slash}RPD5{slash}RD5-Pad82)") (class "Default")
      (node (ref "U1") (pin "82") (pinfunction "*SQICS1/RPD5/RD5_82") (pintype "bidirectional"))
    )
    (net (code "92") (name "unconnected-(U1-AN6{slash}ERXERR{slash}AETXERR{slash}RB11-Pad35)") (class "Default")
      (node (ref "U1") (pin "35") (pinfunction "AN6/ERXERR/AETXERR/RB11_35") (pintype "bidirectional"))
    )
    (net (code "93") (name "unconnected-(U1-AN8{slash}ERXD1{slash}AECOL{slash}RB13-Pad42)") (class "Default")
      (node (ref "U1") (pin "42") (pinfunction "AN8/ERXD1/AECOL/RB13_42") (pintype "bidirectional"))
    )
    (net (code "94") (name "unconnected-(U1-AN23{slash}AERXERR{slash}RG15-Pad1)") (class "Default")
      (node (ref "U1") (pin "1") (pinfunction "AN23/AERXERR/RG15_1") (pintype "bidirectional"))
    )
    (net (code "95") (name "unconnected-(U1-AN32{slash}AETXD0{slash}RPD14{slash}RD14-Pad47)") (class "Default")
      (node (ref "U1") (pin "47") (pinfunction "AN32/AETXD0/RPD14/RD14_47") (pintype "bidirectional"))
    )
    (net (code "96") (name "unconnected-(U1-EBIA0{slash}AN10{slash}ERXD3{slash}AETXD2{slash}RPB15{slash}OCFB{slash}PMA0{slash}RB15-Pad44)") (class "Default")
      (node (ref "U1") (pin "44") (pinfunction "EBIA0/AN10/ERXD3/AETXD2/RPB15/OCFB/PMA0/RB15_44") (pintype "bidirectional"))
    )
    (net (code "97") (name "unconnected-(U1-EBIA4{slash}AN13{slash}C1INC{slash}ECRS{slash}RPG7{slash}SDA4{slash}PMA4{slash}RG7-Pad11)") (class "Default")
      (node (ref "U1") (pin "11") (pinfunction "EBIA4/AN13/C1INC/ECRS/RPG7/SDA4/PMA4/RG7_11") (pintype "bidirectional"))
    )
    (net (code "98") (name "unconnected-(U1-EBIA7{slash}AN49{slash}RPB9{slash}PMA7{slash}RB9-Pad33)") (class "Default")
      (node (ref "U1") (pin "33") (pinfunction "EBIA7/AN49/RPB9/PMA7/RB9_33") (pintype "bidirectional"))
    )
    (net (code "99") (name "unconnected-(U1-EBIA9{slash}RPF4{slash}SDA5{slash}PMA9{slash}RF4-Pad64)") (class "Default")
      (node (ref "U1") (pin "64") (pinfunction "EBIA9/RPF4/SDA5/PMA9/RF4_64") (pintype "bidirectional"))
    )
    (net (code "100") (name "unconnected-(U1-EBIRDY2{slash}RPF8{slash}SCL3{slash}RF8-Pad58)") (class "Default")
      (node (ref "U1") (pin "58") (pinfunction "EBIRDY2/RPF8/SCL3/RF8_58") (pintype "bidirectional"))
    )
    (net (code "101") (name "unconnected-(U1-EBIRDY3{slash}RPF2{slash}SDA3{slash}RF2-Pad57)") (class "Default")
      (node (ref "U1") (pin "57") (pinfunction "EBIRDY3/RPF2/SDA3/RF2_57") (pintype "bidirectional"))
    )
    (net (code "102") (name "unconnected-(U1-EMDIO{slash}AEMDIO{slash}RPD0{slash}RTCC{slash}INT0{slash}RD0-Pad71)") (class "Default")
      (node (ref "U1") (pin "71") (pinfunction "EMDIO/AEMDIO/RPD0/RTCC/INT0/RD0_71") (pintype "bidirectional"))
    )
    (net (code "103") (name "unconnected-(U1-TDI{slash}EBIA18{slash}AN30{slash}RPF13{slash}SCK5{slash}RF13-Pad39)") (class "Default")
      (node (ref "U1") (pin "39") (pinfunction "TDI/EBIA18/AN30/RPF13/SCK5/RF13_39") (pintype "bidirectional"))
    )
    (net (code "104") (name "unconnected-(U1-TRCLK{slash}SQICLK{slash}RA6-Pad89)") (class "Default")
      (node (ref "U1") (pin "89") (pinfunction "TRCLK/SQICLK/RA6_89") (pintype "bidirectional"))
    )
    (net (code "105") (name "unconnected-(U1-TRD0{slash}SQID0{slash}RG13-Pad97)") (class "Default")
      (node (ref "U1") (pin "97") (pinfunction "TRD0/SQID0/RG13_97") (pintype "bidirectional"))
    )
    (net (code "106") (name "unconnected-(U1-TRD1{slash}SQID1{slash}RG12-Pad96)") (class "Default")
      (node (ref "U1") (pin "96") (pinfunction "TRD1/SQID1/RG12_96") (pintype "bidirectional"))
    )
    (net (code "107") (name "unconnected-(U1-TRD2{slash}SQID2{slash}RG14-Pad95)") (class "Default")
      (node (ref "U1") (pin "95") (pinfunction "TRD2/SQID2/RG14_95") (pintype "bidirectional"))
    )
    (net (code "108") (name "unconnected-(U1-TRD3{slash}SQID3{slash}RA7-Pad90)") (class "Default")
      (node (ref "U1") (pin "90") (pinfunction "TRD3/SQID3/RA7_90") (pintype "bidirectional"))
    )
    (net (code "109") (name "unconnected-(USB1-Pad6)") (class "Default")
      (node (ref "USB1") (pin "6") (pinfunction "6_6") (pintype "passive"))
    )
    (net (code "110") (name "~{FAULT1}") (class "Default")
      (node (ref "SV1") (pin "14") (pinfunction "14_14") (pintype "passive"))
      (node (ref "U1") (pin "17") (pinfunction "TMS/EBIA16/AN24/RA0_17") (pintype "bidirectional"))
    )
    (net (code "111") (name "~{FAULT2}") (class "Default")
      (node (ref "SV1") (pin "5") (pinfunction "5_5") (pintype "passive"))
      (node (ref "U1") (pin "60") (pinfunction "EBIRDY1/SDA2/RA3_60") (pintype "bidirectional"))
    )
    (net (code "112") (name "~{SY_FLT1}") (class "Default")
      (node (ref "SV1") (pin "12") (pinfunction "12_12") (pintype "passive"))
      (node (ref "U1") (pin "59") (pinfunction "*EBICS0/SCL2/RA2_59") (pintype "bidirectional"))
    )
    (net (code "113") (name "~{SY_FLT2}") (class "Default")
      (node (ref "SV1") (pin "7") (pinfunction "7_7") (pintype "passive"))
      (node (ref "U1") (pin "2") (pinfunction "EBIA5/AN34/PMA5/RA5_2") (pintype "bidirectional"))
    )
  )
)
